# Main.net
KiCad netlist of a schematic drawn in Altium Designer
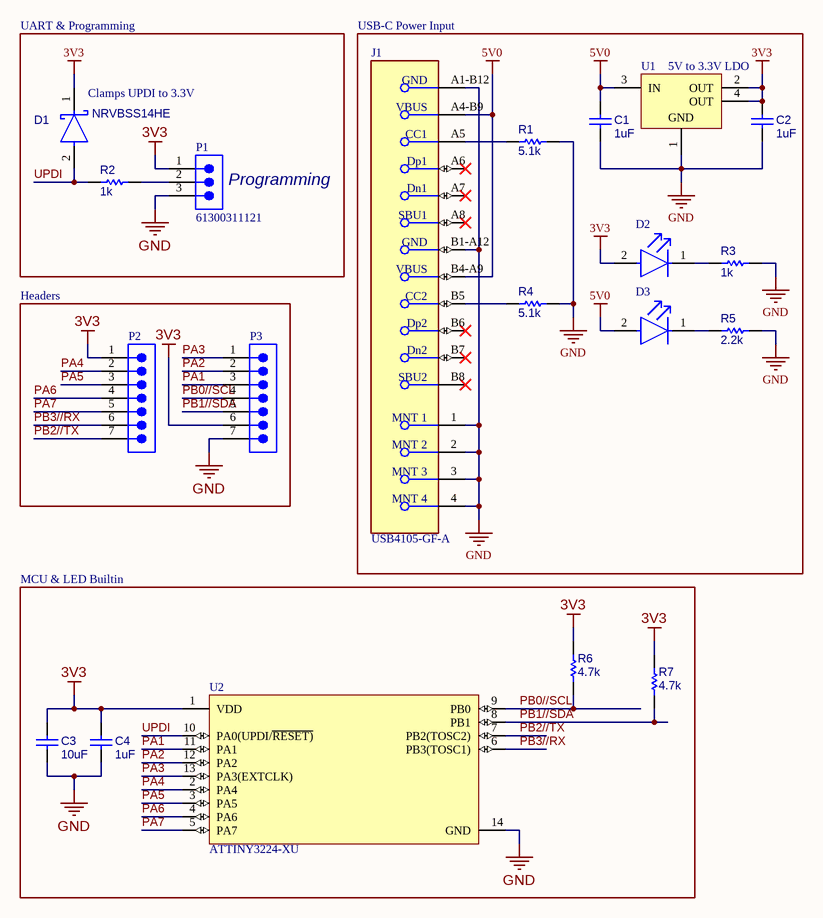
[diagram p0: Main.SchDoc]

(export (version "E")
  (design (tool "Eeschema 10.0.6"))
  (components
    (comp (ref "C1")
      (value "1uF")
      (footprint "WCAP-CSGP_0603_L1.6W0.8H0.8_Reflow")
      (description "10V tolerance")
      (libsource (lib "Altium Content Vault") (part "Capacitor_Non-Polarized"))
    )
    (comp (ref "C2")
      (value "1uF")
      (footprint "WCAP-CSGP_0603_L1.6W0.8H0.8_Reflow")
      (description "10V tolerance")
      (libsource (lib "Altium Content Vault") (part "Capacitor_Non-Polarized"))
    )
    (comp (ref "C3")
      (value "10uF")
      (footprint "WCAP-CSGP_0603_L1.6W0.8H0.8_Reflow")
      (description "10V tolerance")
      (libsource (lib "Altium Content Vault") (part "Capacitor_Non-Polarized"))
    )
    (comp (ref "C4")
      (value "1uF")
      (footprint "WCAP-CSGP_0603_L1.6W0.8H0.8_Reflow")
      (description "10V tolerance")
      (libsource (lib "Altium Content Vault") (part "Capacitor_Non-Polarized"))
    )
    (comp (ref "D1")
      (value "NRVBSS14HE")
      (footprint "FP-477AD-MFG")
      (description "NRVBSS14HE Rectifier Diode, Schottky, 1 Phase, 1 Element, 1A, 40V V(RRM), Silicon")
      (libsource (lib "Altium Content Vault") (part "c1678fac7984e62e0809fbf79c06691"))
    )
    (comp (ref "D2")
      (value "LTST-C190KGKT")
      (footprint "FP-LTST-C190KGKT-MFG")
      (description "LED GREEN CLEAR CHIP SMD")
      (libsource (lib "Altium Content Vault") (part "8706943c75ba83719d021d2fdc84c58"))
    )
    (comp (ref "D3")
      (value "LTST-C190KGKT")
      (footprint "FP-LTST-C190KGKT-MFG")
      (description "LED GREEN CLEAR CHIP SMD")
      (libsource (lib "Altium Content Vault") (part "8706943c75ba83719d021d2fdc84c58"))
    )
    (comp (ref "J1")
      (value "USB4105-GF-A")
      (footprint "FP-USB4105-GF-A-MFG")
      (description "CONN RCPT USB2.0 TYPEC 5A")
      (fields
        (field (name "MANUFACTURER") "GCT")
        (field (name "OCTOPART") "https://octopart.com/usb4105-gf-a-gct-106627878")
      )
      (libsource (lib "Altium Content Vault") (part "e7c17a616881a82b79941196b4bec10"))
    )
    (comp (ref "P1")
      (value "61300311121")
      (footprint "61300311121")
      (description "THT Vertical Pin Header WR-PHD, Pitch 2.54 mm, Single Row, 3 pins")
      (libsource (lib "Altium Content Vault") (part "Header_Male_1R_03P"))
    )
    (comp (ref "P2")
      (value "61300711121")
      (footprint "61300711121")
      (description "THT Vertical Pin Header WR-PHD, Pitch 2.54 mm, Single Row, 7 pins")
      (libsource (lib "Altium Content Vault") (part "Header_Male_1R_07P"))
    )
    (comp (ref "P3")
      (value "61300711121")
      (footprint "61300711121")
      (description "THT Vertical Pin Header WR-PHD, Pitch 2.54 mm, Single Row, 7 pins")
      (libsource (lib "Altium Content Vault") (part "Header_Male_1R_07P"))
    )
    (comp (ref "R1")
      (value "5.1k")
      (footprint "RESC1608X55X25NL10T15")
      (libsource (lib "Altium Content Vault") (part "RES"))
    )
    (comp (ref "R2")
      (value "1k")
      (footprint "RESC1608X55X25NL10T15")
      (libsource (lib "Altium Content Vault") (part "RES"))
    )
    (comp (ref "R3")
      (value "1k")
      (footprint "RESC1608X55X25NL10T15")
      (libsource (lib "Altium Content Vault") (part "RES"))
    )
    (comp (ref "R4")
      (value "5.1k")
      (footprint "RESC1608X55X25NL10T15")
      (libsource (lib "Altium Content Vault") (part "RES"))
    )
    (comp (ref "R5")
      (value "2.2k")
      (footprint "RESC1608X55X25NL10T15")
      (libsource (lib "Altium Content Vault") (part "RES"))
    )
    (comp (ref "R6")
      (value "4.7k")
      (footprint "RESC1608X55X25NL10T15")
      (libsource (lib "Altium Content Vault") (part "RES"))
    )
    (comp (ref "R7")
      (value "4.7k")
      (footprint "RESC1608X55X25NL10T15")
      (libsource (lib "Altium Content Vault") (part "RES"))
    )
    (comp (ref "U1")
      (value "TLV1117LV33DCYR")
      (footprint "DCY0004A_N")
      (fields (field (name "MANUFACTURER") "Texas Instruments"))
      (libsource (lib "Altium Content Vault") (part "TI-TLV1117LV33DCY4"))
    )
    (comp (ref "U2")
      (value "ATTINY3224-XU")
      (footprint "FP-C04-087-ST-MFG")
      (description "ATTINY3224-XU Microcontroller 8-Bit AVR RISC 32KB Flash 1.8V to 5.5V 14-Pin TSSOP Tube")
      (libsource (lib "Altium Content Vault") (part "af96ba96504569538fca35b5c374a83"))
    )
  )
  (nets
    (net (code "1") (name "/PA1") (class "Default")
      (node (ref "P3") (pin "3") (pinfunction "3_3") (pintype "passive"))
      (node (ref "U2") (pin "11") (pinfunction "PA1_11") (pintype "bidirectional"))
    )
    (net (code "2") (name "/PA2") (class "Default")
      (node (ref "P3") (pin "2") (pinfunction "2_2") (pintype "passive"))
      (node (ref "U2") (pin "12") (pinfunction "PA2_12") (pintype "bidirectional"))
    )
    (net (code "3") (name "/PA3") (class "Default")
      (node (ref "P3") (pin "1") (pinfunction "1_1") (pintype "passive"))
      (node (ref "U2") (pin "13") (pinfunction "PA3(EXTCLK)_13") (pintype "bidirectional"))
    )
    (net (code "4") (name "/PA4") (class "Default")
      (node (ref "P2") (pin "2") (pinfunction "2_2") (pintype "passive"))
      (node (ref "U2") (pin "2") (pinfunction "PA4_2") (pintype "bidirectional"))
    )
    (net (code "5") (name "/PA5") (class "Default")
      (node (ref "P2") (pin "3") (pinfunction "3_3") (pintype "passive"))
      (node (ref "U2") (pin "3") (pinfunction "PA5_3") (pintype "bidirectional"))
    )
    (net (code "6") (name "/PA6") (class "Default")
      (node (ref "P2") (pin "4") (pinfunction "4_4") (pintype "passive"))
      (node (ref "U2") (pin "4") (pinfunction "PA6_4") (pintype "bidirectional"))
    )
    (net (code "7") (name "/PA7") (class "Default")
      (node (ref "P2") (pin "5") (pinfunction "5_5") (pintype "passive"))
      (node (ref "U2") (pin "5") (pinfunction "PA7_5") (pintype "bidirectional"))
    )
    (net (code "8") (name "/PB0{slash}{slash}SCL") (class "Default")
      (node (ref "P3") (pin "4") (pinfunction "4_4") (pintype "passive"))
      (node (ref "R6") (pin "1") (pinfunction "1_1") (pintype "passive"))
      (node (ref "U2") (pin "9") (pinfunction "PB0_9") (pintype "bidirectional"))
    )
    (net (code "9") (name "/PB1{slash}{slash}SDA") (class "Default")
      (node (ref "P3") (pin "5") (pinfunction "5_5") (pintype "passive"))
      (node (ref "R7") (pin "1") (pinfunction "1_1") (pintype "passive"))
      (node (ref "U2") (pin "8") (pinfunction "PB1_8") (pintype "bidirectional"))
    )
    (net (code "10") (name "/PB2{slash}{slash}TX") (class "Default")
      (node (ref "P2") (pin "7") (pinfunction "7_7") (pintype "passive"))
      (node (ref "U2") (pin "7") (pinfunction "PB2(TOSC2)_7") (pintype "bidirectional"))
    )
    (net (code "11") (name "/PB3{slash}{slash}RX") (class "Default")
      (node (ref "P2") (pin "6") (pinfunction "6_6") (pintype "passive"))
      (node (ref "U2") (pin "6") (pinfunction "PB3(TOSC1)_6") (pintype "bidirectional"))
    )
    (net (code "12") (name "/UPDI") (class "Default")
      (node (ref "D1") (pin "2") (pinfunction "A_2") (pintype "passive"))
      (node (ref "R2") (pin "2") (pinfunction "2_2") (pintype "passive"))
      (node (ref "U2") (pin "10") (pinfunction "PA0(UPDI/~{RESET)}_10") (pintype "bidirectional"))
    )
    (net (code "13") (name "3V3") (class "Default")
      (node (ref "C2") (pin "2") (pinfunction "2_2") (pintype "passive"))
      (node (ref "C3") (pin "2") (pinfunction "2_2") (pintype "passive"))
      (node (ref "C4") (pin "2") (pinfunction "2_2") (pintype "passive"))
      (node (ref "D1") (pin "1") (pinfunction "C_1") (pintype "passive"))
      (node (ref "D2") (pin "2") (pinfunction "A_2") (pintype "passive"))
      (node (ref "P1") (pin "1") (pinfunction "1_1") (pintype "passive"))
      (node (ref "P2") (pin "1") (pinfunction "1_1") (pintype "passive"))
      (node (ref "P3") (pin "6") (pinfunction "6_6") (pintype "passive"))
      (node (ref "R6") (pin "2") (pinfunction "2_2") (pintype "passive"))
      (node (ref "R7") (pin "2") (pinfunction "2_2") (pintype "passive"))
      (node (ref "U1") (pin "2") (pinfunction "OUT_2") (pintype "power_in"))
      (node (ref "U1") (pin "4") (pinfunction "OUT_4") (pintype "power_in"))
      (node (ref "U2") (pin "1") (pinfunction "VDD_1") (pintype "power_in"))
    )
    (net (code "14") (name "5V0") (class "Default")
      (node (ref "C1") (pin "2") (pinfunction "2_2") (pintype "passive"))
      (node (ref "D3") (pin "2") (pinfunction "A_2") (pintype "passive"))
      (node (ref "J1") (pin "A4-B9") (pinfunction "VBUS_A4-B9") (pintype "power_in"))
      (node (ref "J1") (pin "B4-A9") (pinfunction "VBUS_B4-A9") (pintype "bidirectional"))
      (node (ref "U1") (pin "3") (pinfunction "IN_3") (pintype "power_in"))
    )
    (net (code "15") (name "GND") (class "Default")
      (node (ref "C1") (pin "1") (pinfunction "1_1") (pintype "passive"))
      (node (ref "C2") (pin "1") (pinfunction "1_1") (pintype "passive"))
      (node (ref "C3") (pin "1") (pinfunction "1_1") (pintype "passive"))
      (node (ref "C4") (pin "1") (pinfunction "1_1") (pintype "passive"))
      (node (ref "J1") (pin "1") (pinfunction "MNT_1_1") (pintype "power_in"))
      (node (ref "J1") (pin "2") (pinfunction "MNT_2_2") (pintype "power_in"))
      (node (ref "J1") (pin "3") (pinfunction "MNT_3_3") (pintype "power_in"))
      (node (ref "J1") (pin "4") (pinfunction "MNT_4_4") (pintype "power_in"))
      (node (ref "J1") (pin "A1-B12") (pinfunction "GND_A1-B12") (pintype "power_in"))
      (node (ref "J1") (pin "B1-A12") (pinfunction "GND_B1-A12") (pintype "bidirectional"))
      (node (ref "P1") (pin "3") (pinfunction "3_3") (pintype "passive"))
      (node (ref "P3") (pin "7") (pinfunction "7_7") (pintype "passive"))
      (node (ref "R1") (pin "2") (pinfunction "2_2") (pintype "passive"))
      (node (ref "R3") (pin "2") (pinfunction "2_2") (pintype "passive"))
      (node (ref "R4") (pin "2") (pinfunction "2_2") (pintype "passive"))
      (node (ref "R5") (pin "2") (pinfunction "2_2") (pintype "passive"))
      (node (ref "U1") (pin "1") (pinfunction "GND_1") (pintype "power_in"))
      (node (ref "U2") (pin "14") (pinfunction "GND_14") (pintype "power_in"))
    )
    (net (code "16") (name "Net-(D2-C)") (class "Default")
      (node (ref "D2") (pin "1") (pinfunction "C_1") (pintype "passive"))
      (node (ref "R3") (pin "1") (pinfunction "1_1") (pintype "passive"))
    )
    (net (code "17") (name "Net-(D3-C)") (class "Default")
      (node (ref "D3") (pin "1") (pinfunction "C_1") (pintype "passive"))
      (node (ref "R5") (pin "1") (pinfunction "1_1") (pintype "passive"))
    )
    (net (code "18") (name "Net-(J1-CC1)") (class "Default")
      (node (ref "J1") (pin "A5") (pinfunction "CC1_A5") (pintype "power_in"))
      (node (ref "R1") (pin "1") (pinfunction "1_1") (pintype "passive"))
    )
    (net (code "19") (name "Net-(J1-CC2)") (class "Default")
      (node (ref "J1") (pin "B5") (pinfunction "CC2_B5") (pintype "bidirectional"))
      (node (ref "R4") (pin "1") (pinfunction "1_1") (pintype "passive"))
    )
    (net (code "20") (name "Net-(P1-Pad2)") (class "Default")
      (node (ref "P1") (pin "2") (pinfunction "2_2") (pintype "passive"))
      (node (ref "R2") (pin "1") (pinfunction "1_1") (pintype "passive"))
    )
    (net (code "21") (name "unconnected-(J1-Dn1-PadA7)") (class "Default")
      (node (ref "J1") (pin "A7") (pinfunction "Dn1_A7") (pintype "bidirectional+no_connect"))
    )
    (net (code "22") (name "unconnected-(J1-Dn2-PadB7)") (class "Default")
      (node (ref "J1") (pin "B7") (pinfunction "Dn2_B7") (pintype "bidirectional+no_connect"))
    )
    (net (code "23") (name "unconnected-(J1-Dp1-PadA6)") (class "Default")
      (node (ref "J1") (pin "A6") (pinfunction "Dp1_A6") (pintype "bidirectional+no_connect"))
    )
    (net (code "24") (name "unconnected-(J1-Dp2-PadB6)") (class "Default")
      (node (ref "J1") (pin "B6") (pinfunction "Dp2_B6") (pintype "bidirectional+no_connect"))
    )
    (net (code "25") (name "unconnected-(J1-SBU1-PadA8)") (class "Default")
      (node (ref "J1") (pin "A8") (pinfunction "SBU1_A8") (pintype "bidirectional+no_connect"))
    )
    (net (code "26") (name "unconnected-(J1-SBU2-PadB8)") (class "Default")
      (node (ref "J1") (pin "B8") (pinfunction "SBU2_B8") (pintype "power_in+no_connect"))
    )
  )
)
